# drill-rev-1.net
KiCad netlist of a schematic drawn in EAGLE
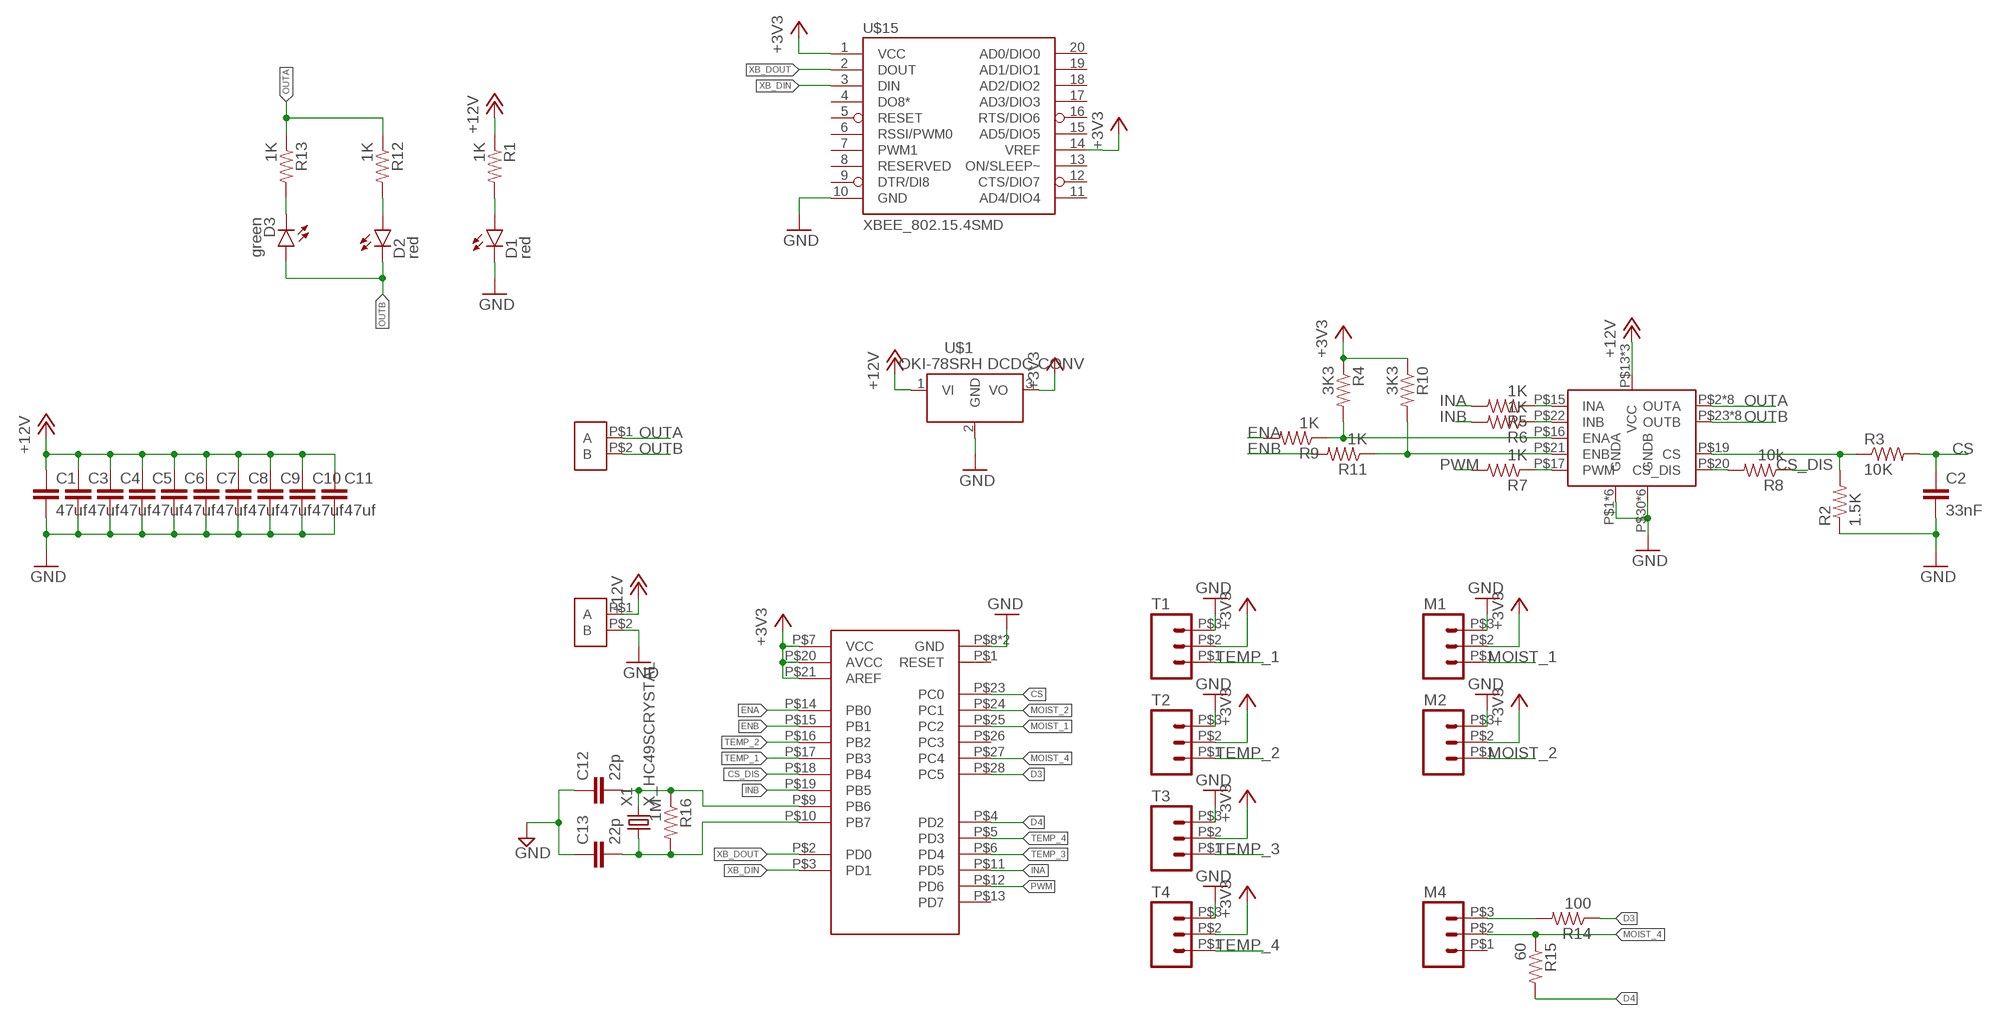
[diagram p0: schematic, sheet 1]

(export (version "E")
  (design (tool "Eeschema 10.0.6"))
  (components
    (comp (ref "C1")
      (value "47uf")
      (footprint "eagle-import:1210")
      (libsource (lib "eagle-import") (part "CAP1210"))
    )
    (comp (ref "C2")
      (value "33nF")
      (footprint "eagle-import:0603-CAP")
      (libsource (lib "eagle-import") (part "CAP0603-CAP"))
    )
    (comp (ref "C3")
      (value "47uf")
      (footprint "eagle-import:1210")
      (libsource (lib "eagle-import") (part "CAP1210"))
    )
    (comp (ref "C4")
      (value "47uf")
      (footprint "eagle-import:1210")
      (libsource (lib "eagle-import") (part "CAP1210"))
    )
    (comp (ref "C5")
      (value "47uf")
      (footprint "eagle-import:1210")
      (libsource (lib "eagle-import") (part "CAP1210"))
    )
    (comp (ref "C6")
      (value "47uf")
      (footprint "eagle-import:1210")
      (libsource (lib "eagle-import") (part "CAP1210"))
    )
    (comp (ref "C7")
      (value "47uf")
      (footprint "eagle-import:1210")
      (libsource (lib "eagle-import") (part "CAP1210"))
    )
    (comp (ref "C8")
      (value "47uf")
      (footprint "eagle-import:1210")
      (libsource (lib "eagle-import") (part "CAP1210"))
    )
    (comp (ref "C9")
      (value "47uf")
      (footprint "eagle-import:1210")
      (libsource (lib "eagle-import") (part "CAP1210"))
    )
    (comp (ref "C10")
      (value "47uf")
      (footprint "eagle-import:1210")
      (libsource (lib "eagle-import") (part "CAP1210"))
    )
    (comp (ref "C11")
      (value "47uf")
      (footprint "eagle-import:1210")
      (libsource (lib "eagle-import") (part "CAP1210"))
    )
    (comp (ref "C12")
      (value "22p")
      (footprint "eagle-import:0603-CAP")
      (libsource (lib "eagle-import") (part "CAP0603-CAP"))
    )
    (comp (ref "C13")
      (value "22p")
      (footprint "eagle-import:0603-CAP")
      (libsource (lib "eagle-import") (part "CAP0603-CAP"))
    )
    (comp (ref "D1")
      (value "red")
      (footprint "eagle-import:LED-0603")
      (libsource (lib "eagle-import") (part "LED0603"))
    )
    (comp (ref "D2")
      (value "red")
      (footprint "eagle-import:LED-0603")
      (libsource (lib "eagle-import") (part "LED0603"))
    )
    (comp (ref "D3")
      (value "green")
      (footprint "eagle-import:LED-0603")
      (libsource (lib "eagle-import") (part "LED0603"))
    )
    (comp (ref "M1")
      (value "M03VERT")
      (footprint "eagle-import:MOLEX0436500328")
      (libsource (lib "eagle-import") (part "M03VERT"))
    )
    (comp (ref "M2")
      (value "M03VERT")
      (footprint "eagle-import:MOLEX0436500328")
      (libsource (lib "eagle-import") (part "M03VERT"))
    )
    (comp (ref "M4")
      (value "M03VERT")
      (footprint "eagle-import:MOLEX0436500328")
      (libsource (lib "eagle-import") (part "M03VERT"))
    )
    (comp (ref "R1")
      (value "1K")
      (footprint "eagle-import:0603-RES")
      (libsource (lib "eagle-import") (part "RESISTOR0603"))
    )
    (comp (ref "R2")
      (value "1.5K")
      (footprint "eagle-import:0603-RES")
      (libsource (lib "eagle-import") (part "RESISTOR0603"))
    )
    (comp (ref "R3")
      (value "10K")
      (footprint "eagle-import:0603-RES")
      (libsource (lib "eagle-import") (part "RESISTOR0603"))
    )
    (comp (ref "R4")
      (value "3K3")
      (footprint "eagle-import:0603-RES")
      (libsource (lib "eagle-import") (part "RESISTOR0603"))
    )
    (comp (ref "R5")
      (value "1K")
      (footprint "eagle-import:0603-RES")
      (libsource (lib "eagle-import") (part "RESISTOR0603"))
    )
    (comp (ref "R6")
      (value "1K")
      (footprint "eagle-import:0603-RES")
      (libsource (lib "eagle-import") (part "RESISTOR0603"))
    )
    (comp (ref "R7")
      (value "1K")
      (footprint "eagle-import:0603-RES")
      (libsource (lib "eagle-import") (part "RESISTOR0603"))
    )
    (comp (ref "R8")
      (value "10k")
      (footprint "eagle-import:0603-RES")
      (libsource (lib "eagle-import") (part "RESISTOR0603"))
    )
    (comp (ref "R9")
      (value "1K")
      (footprint "eagle-import:0603-RES")
      (libsource (lib "eagle-import") (part "RESISTOR0603"))
    )
    (comp (ref "R10")
      (value "3K3")
      (footprint "eagle-import:0603-RES")
      (libsource (lib "eagle-import") (part "RESISTOR0603"))
    )
    (comp (ref "R11")
      (value "1K")
      (footprint "eagle-import:0603-RES")
      (libsource (lib "eagle-import") (part "RESISTOR0603"))
    )
    (comp (ref "R12")
      (value "1K")
      (footprint "eagle-import:0603-RES")
      (libsource (lib "eagle-import") (part "RESISTOR0603"))
    )
    (comp (ref "R13")
      (value "1K")
      (footprint "eagle-import:0603-RES")
      (libsource (lib "eagle-import") (part "RESISTOR0603"))
    )
    (comp (ref "R14")
      (value "100")
      (footprint "eagle-import:1206")
      (libsource (lib "eagle-import") (part "RESISTOR1206"))
    )
    (comp (ref "R15")
      (value "60")
      (footprint "eagle-import:1206")
      (libsource (lib "eagle-import") (part "RESISTOR1206"))
    )
    (comp (ref "R16")
      (value "1M")
      (footprint "eagle-import:0603-RES")
      (libsource (lib "eagle-import") (part "RESISTOR0603"))
    )
    (comp (ref "T1")
      (value "M03VERT")
      (footprint "eagle-import:MOLEX0436500328")
      (libsource (lib "eagle-import") (part "M03VERT"))
    )
    (comp (ref "T2")
      (value "M03VERT")
      (footprint "eagle-import:MOLEX0436500328")
      (libsource (lib "eagle-import") (part "M03VERT"))
    )
    (comp (ref "T3")
      (value "M03VERT")
      (footprint "eagle-import:MOLEX0436500328")
      (libsource (lib "eagle-import") (part "M03VERT"))
    )
    (comp (ref "T4")
      (value "M03VERT")
      (footprint "eagle-import:MOLEX0436500328")
      (libsource (lib "eagle-import") (part "M03VERT"))
    )
    (comp (ref "U$1")
      (value "Q_OKI-78SR")
      (footprint "eagle-import:OKI-78SR_HORIZ")
      (libsource (lib "eagle-import") (part "Q_OKI-78SR"))
    )
    (comp (ref "U$3")
      (value "TE_2POS-5MM_SCREW_TERM")
      (footprint "eagle-import:TE_2POS-5MM_SCREW_TERM")
      (libsource (lib "eagle-import") (part "TE_2POS-5MM_SCREW_TERM"))
    )
    (comp (ref "U$5")
      (value "TE_2POS-5MM_SCREW_TERM")
      (footprint "eagle-import:TE_2POS-5MM_SCREW_TERM")
      (libsource (lib "eagle-import") (part "TE_2POS-5MM_SCREW_TERM"))
    )
    (comp (ref "U$6")
      (value "VNH5XXX_HBRIDGEVNH5050A")
      (footprint "eagle-import:POWERSSO-36_TP")
      (libsource (lib "eagle-import") (part "VNH5XXX_HBRIDGEVNH5050A"))
    )
    (comp (ref "U$13")
      (value "DIP_SKT_ATMEGA")
      (footprint "eagle-import:DIP_SKT_ATMEGA")
      (libsource (lib "eagle-import") (part "DIP_SKT_ATMEGA"))
    )
    (comp (ref "U$15")
      (value "XBEE_802.15.4SMD")
      (footprint "eagle-import:XBEE_802.15.4_SMD")
      (libsource (lib "eagle-import") (part "XBEE_802.15.4SMD"))
    )
    (comp (ref "X1")
      (value "X_HC49SCRYSTAL")
      (footprint "eagle-import:HC-49")
      (libsource (lib "eagle-import") (part "X_HC49SCRYSTAL"))
    )
  )
  (nets
    (net (code "1") (name "+3V3") (class "Default")
      (node (ref "M1") (pin "P$2") (pinfunction "2_P$2") (pintype "passive"))
      (node (ref "M2") (pin "P$2") (pinfunction "2_P$2") (pintype "passive"))
      (node (ref "R10") (pin "1") (pinfunction "1_1") (pintype "passive"))
      (node (ref "R4") (pin "1") (pinfunction "1_1") (pintype "passive"))
      (node (ref "T1") (pin "P$2") (pinfunction "2_P$2") (pintype "passive"))
      (node (ref "T2") (pin "P$2") (pinfunction "2_P$2") (pintype "passive"))
      (node (ref "T3") (pin "P$2") (pinfunction "2_P$2") (pintype "passive"))
      (node (ref "T4") (pin "P$2") (pinfunction "2_P$2") (pintype "passive"))
      (node (ref "U$1") (pin "3") (pinfunction "VO_3") (pintype "bidirectional"))
      (node (ref "U$13") (pin "P$20") (pinfunction "AVCC_P$20") (pintype "bidirectional"))
      (node (ref "U$13") (pin "P$21") (pinfunction "AREF_P$21") (pintype "bidirectional"))
      (node (ref "U$13") (pin "P$7") (pinfunction "VCC_P$7") (pintype "bidirectional"))
      (node (ref "U$15") (pin "1") (pinfunction "VCC_1") (pintype "power_in"))
      (node (ref "U$15") (pin "14") (pinfunction "VREF_14") (pintype "bidirectional"))
    )
    (net (code "2") (name "+12V") (class "Default")
      (node (ref "C1") (pin "1") (pinfunction "1_1") (pintype "passive"))
      (node (ref "C10") (pin "1") (pinfunction "1_1") (pintype "passive"))
      (node (ref "C11") (pin "1") (pinfunction "1_1") (pintype "passive"))
      (node (ref "C3") (pin "1") (pinfunction "1_1") (pintype "passive"))
      (node (ref "C4") (pin "1") (pinfunction "1_1") (pintype "passive"))
      (node (ref "C5") (pin "1") (pinfunction "1_1") (pintype "passive"))
      (node (ref "C6") (pin "1") (pinfunction "1_1") (pintype "passive"))
      (node (ref "C7") (pin "1") (pinfunction "1_1") (pintype "passive"))
      (node (ref "C8") (pin "1") (pinfunction "1_1") (pintype "passive"))
      (node (ref "C9") (pin "1") (pinfunction "1_1") (pintype "passive"))
      (node (ref "R1") (pin "1") (pinfunction "1_1") (pintype "passive"))
      (node (ref "U$1") (pin "1") (pinfunction "VI_1") (pintype "bidirectional"))
      (node (ref "U$5") (pin "P$1") (pinfunction "A_P$1") (pintype "bidirectional"))
      (node (ref "U$6") (pin "P$13") (pinfunction "VCC_P$13") (pintype "bidirectional"))
      (node (ref "U$6") (pin "P$24") (pinfunction "VCC_P$24") (pintype "bidirectional"))
      (node (ref "U$6") (pin "SLUG1") (pinfunction "VCC_SLUG1") (pintype "bidirectional"))
    )
    (net (code "3") (name "CS") (class "Default")
      (node (ref "C2") (pin "1") (pinfunction "1_1") (pintype "passive"))
      (node (ref "R3") (pin "2") (pinfunction "2_2") (pintype "passive"))
      (node (ref "U$13") (pin "P$23") (pinfunction "PC0_P$23") (pintype "bidirectional"))
    )
    (net (code "4") (name "CS_DIS") (class "Default")
      (node (ref "R8") (pin "1") (pinfunction "1_1") (pintype "passive"))
      (node (ref "U$13") (pin "P$18") (pinfunction "PB4_P$18") (pintype "bidirectional"))
    )
    (net (code "5") (name "D3") (class "Default")
      (node (ref "R14") (pin "1") (pinfunction "1_1") (pintype "passive"))
      (node (ref "U$13") (pin "P$28") (pinfunction "PC5_P$28") (pintype "bidirectional"))
    )
    (net (code "6") (name "D4") (class "Default")
      (node (ref "R15") (pin "2") (pinfunction "2_2") (pintype "passive"))
      (node (ref "U$13") (pin "P$4") (pinfunction "PD2_P$4") (pintype "bidirectional"))
    )
    (net (code "7") (name "ENA") (class "Default")
      (node (ref "R9") (pin "2") (pinfunction "2_2") (pintype "passive"))
      (node (ref "U$13") (pin "P$14") (pinfunction "PB0_P$14") (pintype "bidirectional"))
    )
    (net (code "8") (name "ENB") (class "Default")
      (node (ref "R11") (pin "2") (pinfunction "2_2") (pintype "passive"))
      (node (ref "U$13") (pin "P$15") (pinfunction "PB1_P$15") (pintype "bidirectional"))
    )
    (net (code "9") (name "GND") (class "Default")
      (node (ref "C1") (pin "2") (pinfunction "2_2") (pintype "passive"))
      (node (ref "C10") (pin "2") (pinfunction "2_2") (pintype "passive"))
      (node (ref "C11") (pin "2") (pinfunction "2_2") (pintype "passive"))
      (node (ref "C12") (pin "1") (pinfunction "1_1") (pintype "passive"))
      (node (ref "C13") (pin "1") (pinfunction "1_1") (pintype "passive"))
      (node (ref "C2") (pin "2") (pinfunction "2_2") (pintype "passive"))
      (node (ref "C3") (pin "2") (pinfunction "2_2") (pintype "passive"))
      (node (ref "C4") (pin "2") (pinfunction "2_2") (pintype "passive"))
      (node (ref "C5") (pin "2") (pinfunction "2_2") (pintype "passive"))
      (node (ref "C6") (pin "2") (pinfunction "2_2") (pintype "passive"))
      (node (ref "C7") (pin "2") (pinfunction "2_2") (pintype "passive"))
      (node (ref "C8") (pin "2") (pinfunction "2_2") (pintype "passive"))
      (node (ref "C9") (pin "2") (pinfunction "2_2") (pintype "passive"))
      (node (ref "D1") (pin "C") (pinfunction "C_C") (pintype "passive"))
      (node (ref "M1") (pin "P$3") (pinfunction "3_P$3") (pintype "passive"))
      (node (ref "M2") (pin "P$3") (pinfunction "3_P$3") (pintype "passive"))
      (node (ref "R2") (pin "1") (pinfunction "1_1") (pintype "passive"))
      (node (ref "T1") (pin "P$3") (pinfunction "3_P$3") (pintype "passive"))
      (node (ref "T2") (pin "P$3") (pinfunction "3_P$3") (pintype "passive"))
      (node (ref "T3") (pin "P$3") (pinfunction "3_P$3") (pintype "passive"))
      (node (ref "T4") (pin "P$3") (pinfunction "3_P$3") (pintype "passive"))
      (node (ref "U$1") (pin "2") (pinfunction "GND_2") (pintype "bidirectional"))
      (node (ref "U$13") (pin "P$22") (pinfunction "GND_P$22") (pintype "bidirectional"))
      (node (ref "U$13") (pin "P$8") (pinfunction "GND_P$8") (pintype "bidirectional"))
      (node (ref "U$15") (pin "10") (pinfunction "GND_10") (pintype "power_in"))
      (node (ref "U$5") (pin "P$2") (pinfunction "B_P$2") (pintype "bidirectional"))
      (node (ref "U$6") (pin "P$1") (pinfunction "GNDA_P$1") (pintype "bidirectional"))
      (node (ref "U$6") (pin "P$3") (pinfunction "GNDA_P$3") (pintype "bidirectional"))
      (node (ref "U$6") (pin "P$30") (pinfunction "GNDB_P$30") (pintype "bidirectional"))
      (node (ref "U$6") (pin "P$31") (pinfunction "GNDB_P$31") (pintype "bidirectional"))
      (node (ref "U$6") (pin "P$32") (pinfunction "GNDB_P$32") (pintype "bidirectional"))
      (node (ref "U$6") (pin "P$33") (pinfunction "GNDB_P$33") (pintype "bidirectional"))
      (node (ref "U$6") (pin "P$34") (pinfunction "GNDB_P$34") (pintype "bidirectional"))
      (node (ref "U$6") (pin "P$36") (pinfunction "GNDB_P$36") (pintype "bidirectional"))
      (node (ref "U$6") (pin "P$4") (pinfunction "GNDA_P$4") (pintype "bidirectional"))
      (node (ref "U$6") (pin "P$5") (pinfunction "GNDA_P$5") (pintype "bidirectional"))
      (node (ref "U$6") (pin "P$6") (pinfunction "GNDA_P$6") (pintype "bidirectional"))
      (node (ref "U$6") (pin "P$7") (pinfunction "GNDA_P$7") (pintype "bidirectional"))
    )
    (net (code "10") (name "INA") (class "Default")
      (node (ref "R5") (pin "2") (pinfunction "2_2") (pintype "passive"))
      (node (ref "U$13") (pin "P$11") (pinfunction "PD5_P$11") (pintype "bidirectional"))
    )
    (net (code "11") (name "INB") (class "Default")
      (node (ref "R6") (pin "2") (pinfunction "2_2") (pintype "passive"))
      (node (ref "U$13") (pin "P$19") (pinfunction "PB5_P$19") (pintype "bidirectional"))
    )
    (net (code "12") (name "MOIST_1") (class "Default")
      (node (ref "M1") (pin "P$1") (pinfunction "1_P$1") (pintype "passive"))
      (node (ref "U$13") (pin "P$25") (pinfunction "PC2_P$25") (pintype "bidirectional"))
    )
    (net (code "13") (name "MOIST_2") (class "Default")
      (node (ref "M2") (pin "P$1") (pinfunction "1_P$1") (pintype "passive"))
      (node (ref "U$13") (pin "P$24") (pinfunction "PC1_P$24") (pintype "bidirectional"))
    )
    (net (code "14") (name "MOIST_4") (class "Default")
      (node (ref "M4") (pin "P$2") (pinfunction "2_P$2") (pintype "passive"))
      (node (ref "R15") (pin "1") (pinfunction "1_1") (pintype "passive"))
      (node (ref "U$13") (pin "P$27") (pinfunction "PC4_P$27") (pintype "bidirectional"))
    )
    (net (code "15") (name "Net-(D1-PadA)") (class "Default")
      (node (ref "D1") (pin "A") (pinfunction "A_A") (pintype "passive"))
      (node (ref "R1") (pin "2") (pinfunction "2_2") (pintype "passive"))
    )
    (net (code "16") (name "Net-(D2-PadA)") (class "Default")
      (node (ref "D2") (pin "A") (pinfunction "A_A") (pintype "passive"))
      (node (ref "R12") (pin "2") (pinfunction "2_2") (pintype "passive"))
    )
    (net (code "17") (name "Net-(D3-PadC)") (class "Default")
      (node (ref "D3") (pin "C") (pinfunction "C_C") (pintype "passive"))
      (node (ref "R13") (pin "2") (pinfunction "2_2") (pintype "passive"))
    )
    (net (code "18") (name "Net-(M4-3)") (class "Default")
      (node (ref "M4") (pin "P$3") (pinfunction "3_P$3") (pintype "passive"))
      (node (ref "R14") (pin "2") (pinfunction "2_2") (pintype "passive"))
    )
    (net (code "19") (name "Net-(U$6-CS)") (class "Default")
      (node (ref "R2") (pin "2") (pinfunction "2_2") (pintype "passive"))
      (node (ref "R3") (pin "1") (pinfunction "1_1") (pintype "passive"))
      (node (ref "U$6") (pin "P$19") (pinfunction "CS_P$19") (pintype "bidirectional"))
    )
    (net (code "20") (name "Net-(U$6-CS_DIS)") (class "Default")
      (node (ref "R8") (pin "2") (pinfunction "2_2") (pintype "passive"))
      (node (ref "U$6") (pin "P$20") (pinfunction "CS_DIS_P$20") (pintype "bidirectional"))
    )
    (net (code "21") (name "Net-(U$6-ENA)") (class "Default")
      (node (ref "R4") (pin "2") (pinfunction "2_2") (pintype "passive"))
      (node (ref "R9") (pin "1") (pinfunction "1_1") (pintype "passive"))
      (node (ref "U$6") (pin "P$16") (pinfunction "ENA_P$16") (pintype "bidirectional"))
    )
    (net (code "22") (name "Net-(U$6-ENB)") (class "Default")
      (node (ref "R10") (pin "2") (pinfunction "2_2") (pintype "passive"))
      (node (ref "R11") (pin "1") (pinfunction "1_1") (pintype "passive"))
      (node (ref "U$6") (pin "P$21") (pinfunction "ENB_P$21") (pintype "bidirectional"))
    )
    (net (code "23") (name "Net-(U$6-INA)") (class "Default")
      (node (ref "R5") (pin "1") (pinfunction "1_1") (pintype "passive"))
      (node (ref "U$6") (pin "P$15") (pinfunction "INA_P$15") (pintype "bidirectional"))
    )
    (net (code "24") (name "Net-(U$6-INB)") (class "Default")
      (node (ref "R6") (pin "1") (pinfunction "1_1") (pintype "passive"))
      (node (ref "U$6") (pin "P$22") (pinfunction "INB_P$22") (pintype "bidirectional"))
    )
    (net (code "25") (name "Net-(U$6-PWM)") (class "Default")
      (node (ref "R7") (pin "1") (pinfunction "1_1") (pintype "passive"))
      (node (ref "U$6") (pin "P$17") (pinfunction "PWM_P$17") (pintype "bidirectional"))
    )
    (net (code "26") (name "Net-(U$13-PB6)") (class "Default")
      (node (ref "C12") (pin "2") (pinfunction "2_2") (pintype "passive"))
      (node (ref "R16") (pin "1") (pinfunction "1_1") (pintype "passive"))
      (node (ref "U$13") (pin "P$9") (pinfunction "PB6_P$9") (pintype "bidirectional"))
      (node (ref "X1") (pin "P$2") (pinfunction "2_P$2") (pintype "passive"))
    )
    (net (code "27") (name "Net-(U$13-PB7)") (class "Default")
      (node (ref "C13") (pin "2") (pinfunction "2_2") (pintype "passive"))
      (node (ref "R16") (pin "2") (pinfunction "2_2") (pintype "passive"))
      (node (ref "U$13") (pin "P$10") (pinfunction "PB7_P$10") (pintype "bidirectional"))
      (node (ref "X1") (pin "P$1") (pinfunction "1_P$1") (pintype "passive"))
    )
    (net (code "28") (name "OUTA") (class "Default")
      (node (ref "R12") (pin "1") (pinfunction "1_1") (pintype "passive"))
      (node (ref "R13") (pin "1") (pinfunction "1_1") (pintype "passive"))
      (node (ref "U$3") (pin "P$1") (pinfunction "A_P$1") (pintype "bidirectional"))
      (node (ref "U$6") (pin "P$10") (pinfunction "OUTA_P$10") (pintype "bidirectional"))
      (node (ref "U$6") (pin "P$11") (pinfunction "OUTA_P$11") (pintype "bidirectional"))
      (node (ref "U$6") (pin "P$12") (pinfunction "OUTA_P$12") (pintype "bidirectional"))
      (node (ref "U$6") (pin "P$14") (pinfunction "OUTA_P$14") (pintype "bidirectional"))
      (node (ref "U$6") (pin "P$2") (pinfunction "OUTA_P$2") (pintype "bidirectional"))
      (node (ref "U$6") (pin "P$8") (pinfunction "OUTA_P$8") (pintype "bidirectional"))
      (node (ref "U$6") (pin "P$9") (pinfunction "OUTA_P$9") (pintype "bidirectional"))
      (node (ref "U$6") (pin "SLUG2") (pinfunction "OUTA_SLUG2") (pintype "bidirectional"))
    )
    (net (code "29") (name "OUTB") (class "Default")
      (node (ref "D2") (pin "C") (pinfunction "C_C") (pintype "passive"))
      (node (ref "D3") (pin "A") (pinfunction "A_A") (pintype "passive"))
      (node (ref "U$3") (pin "P$2") (pinfunction "B_P$2") (pintype "bidirectional"))
      (node (ref "U$6") (pin "P$23") (pinfunction "OUTB_P$23") (pintype "bidirectional"))
      (node (ref "U$6") (pin "P$25") (pinfunction "OUTB_P$25") (pintype "bidirectional"))
      (node (ref "U$6") (pin "P$26") (pinfunction "OUTB_P$26") (pintype "bidirectional"))
      (node (ref "U$6") (pin "P$27") (pinfunction "OUTB_P$27") (pintype "bidirectional"))
      (node (ref "U$6") (pin "P$28") (pinfunction "OUTB_P$28") (pintype "bidirectional"))
      (node (ref "U$6") (pin "P$29") (pinfunction "OUTB_P$29") (pintype "bidirectional"))
      (node (ref "U$6") (pin "P$35") (pinfunction "OUTB_P$35") (pintype "bidirectional"))
      (node (ref "U$6") (pin "SLUG3") (pinfunction "OUTB_SLUG3") (pintype "bidirectional"))
    )
    (net (code "30") (name "PWM") (class "Default")
      (node (ref "R7") (pin "2") (pinfunction "2_2") (pintype "passive"))
      (node (ref "U$13") (pin "P$12") (pinfunction "PD6_P$12") (pintype "bidirectional"))
    )
    (net (code "31") (name "TEMP_1") (class "Default")
      (node (ref "T1") (pin "P$1") (pinfunction "1_P$1") (pintype "passive"))
      (node (ref "U$13") (pin "P$17") (pinfunction "PB3_P$17") (pintype "bidirectional"))
    )
    (net (code "32") (name "TEMP_2") (class "Default")
      (node (ref "T2") (pin "P$1") (pinfunction "1_P$1") (pintype "passive"))
      (node (ref "U$13") (pin "P$16") (pinfunction "PB2_P$16") (pintype "bidirectional"))
    )
    (net (code "33") (name "TEMP_3") (class "Default")
      (node (ref "T3") (pin "P$1") (pinfunction "1_P$1") (pintype "passive"))
      (node (ref "U$13") (pin "P$6") (pinfunction "PD4_P$6") (pintype "bidirectional"))
    )
    (net (code "34") (name "TEMP_4") (class "Default")
      (node (ref "T4") (pin "P$1") (pinfunction "1_P$1") (pintype "passive"))
      (node (ref "U$13") (pin "P$5") (pinfunction "PD3_P$5") (pintype "bidirectional"))
    )
    (net (code "35") (name "XB_DIN") (class "Default")
      (node (ref "U$13") (pin "P$3") (pinfunction "PD1_P$3") (pintype "bidirectional"))
      (node (ref "U$15") (pin "3") (pinfunction "DIN_3") (pintype "input"))
    )
    (net (code "36") (name "XB_DOUT") (class "Default")
      (node (ref "U$13") (pin "P$2") (pinfunction "PD0_P$2") (pintype "bidirectional"))
      (node (ref "U$15") (pin "2") (pinfunction "DOUT_2") (pintype "output"))
    )
    (net (code "37") (name "unconnected-(M4-1-PadP$1)") (class "Default")
      (node (ref "M4") (pin "P$1") (pinfunction "1_P$1") (pintype "passive"))
    )
    (net (code "38") (name "unconnected-(U$13-PC3-PadP$26)") (class "Default")
      (node (ref "U$13") (pin "P$26") (pinfunction "PC3_P$26") (pintype "bidirectional"))
    )
    (net (code "39") (name "unconnected-(U$13-PD7-PadP$13)") (class "Default")
      (node (ref "U$13") (pin "P$13") (pinfunction "PD7_P$13") (pintype "bidirectional"))
    )
    (net (code "40") (name "unconnected-(U$13-RESET-PadP$1)") (class "Default")
      (node (ref "U$13") (pin "P$1") (pinfunction "RESET_P$1") (pintype "bidirectional"))
    )
    (net (code "41") (name "unconnected-(U$15-AD0{slash}DIO0-Pad20)") (class "Default")
      (node (ref "U$15") (pin "20") (pinfunction "AD0/DIO0_20") (pintype "bidirectional"))
    )
    (net (code "42") (name "unconnected-(U$15-AD1{slash}DIO1-Pad19)") (class "Default")
      (node (ref "U$15") (pin "19") (pinfunction "AD1/DIO1_19") (pintype "bidirectional"))
    )
    (net (code "43") (name "unconnected-(U$15-AD2{slash}DIO2-Pad18)") (class "Default")
      (node (ref "U$15") (pin "18") (pinfunction "AD2/DIO2_18") (pintype "bidirectional"))
    )
    (net (code "44") (name "unconnected-(U$15-AD3{slash}DIO3-Pad17)") (class "Default")
      (node (ref "U$15") (pin "17") (pinfunction "AD3/DIO3_17") (pintype "bidirectional"))
    )
    (net (code "45") (name "unconnected-(U$15-AD4{slash}DIO4-Pad11)") (class "Default")
      (node (ref "U$15") (pin "11") (pinfunction "AD4/DIO4_11") (pintype "bidirectional"))
    )
    (net (code "46") (name "unconnected-(U$15-AD5{slash}DIO5-Pad15)") (class "Default")
      (node (ref "U$15") (pin "15") (pinfunction "AD5/DIO5_15") (pintype "bidirectional"))
    )
    (net (code "47") (name "unconnected-(U$15-CTS{slash}DIO7-Pad12)") (class "Default")
      (node (ref "U$15") (pin "12") (pinfunction "CTS/DIO7_12") (pintype "output"))
    )
    (net (code "48") (name "unconnected-(U$15-DO8*-Pad4)") (class "Default")
      (node (ref "U$15") (pin "4") (pinfunction "DO8*_4") (pintype "bidirectional"))
    )
    (net (code "49") (name "unconnected-(U$15-DTR{slash}DI8-Pad9)") (class "Default")
      (node (ref "U$15") (pin "9") (pinfunction "DTR/DI8_9") (pintype "bidirectional"))
    )
    (net (code "50") (name "unconnected-(U$15-ON{slash}SLEEP~{}-Pad13)") (class "Default")
      (node (ref "U$15") (pin "13") (pinfunction "ON/SLEEP~{}_13") (pintype "bidirectional"))
    )
    (net (code "51") (name "unconnected-(U$15-PWM1-Pad7)") (class "Default")
      (node (ref "U$15") (pin "7") (pinfunction "PWM1_7") (pintype "bidirectional"))
    )
    (net (code "52") (name "unconnected-(U$15-RESERVED-Pad8)") (class "Default")
      (node (ref "U$15") (pin "8") (pinfunction "RESERVED_8") (pintype "bidirectional"))
    )
    (net (code "53") (name "unconnected-(U$15-RESET-Pad5)") (class "Default")
      (node (ref "U$15") (pin "5") (pinfunction "RESET_5") (pintype "input"))
    )
    (net (code "54") (name "unconnected-(U$15-RSSI{slash}PWM0-Pad6)") (class "Default")
      (node (ref "U$15") (pin "6") (pinfunction "RSSI/PWM0_6") (pintype "bidirectional"))
    )
    (net (code "55") (name "unconnected-(U$15-RTS{slash}DIO6-Pad16)") (class "Default")
      (node (ref "U$15") (pin "16") (pinfunction "RTS/DIO6_16") (pintype "input"))
    )
  )
)
